# 4_54.net
KiCad netlist of a schematic drawn in EasyEDA
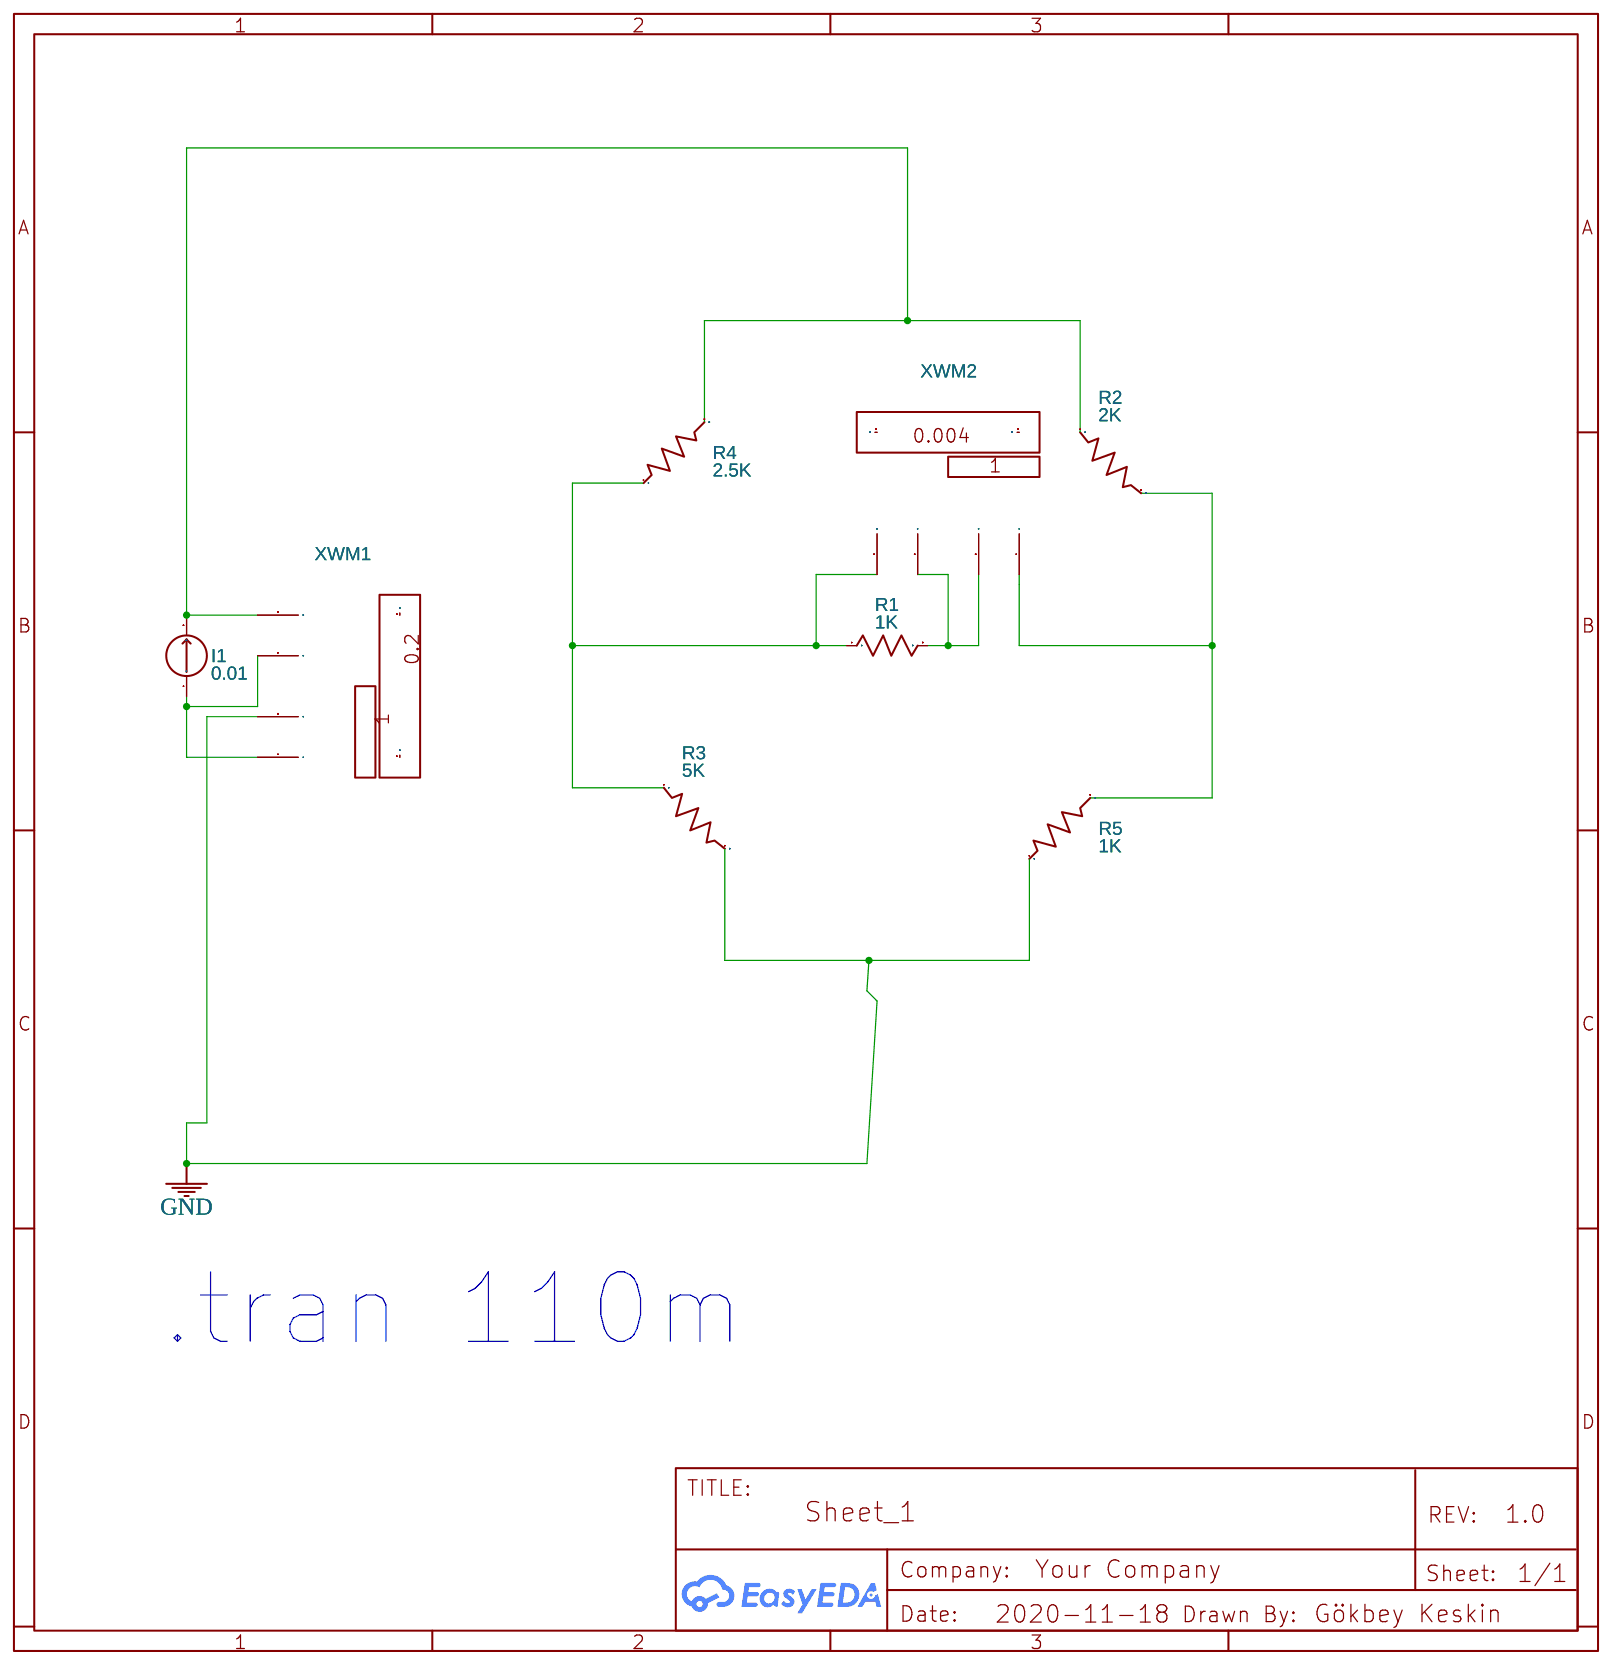
[diagram p0: schematic sheet]

(export (version "E")
  (design (tool "Eeschema 10.0.6"))
  (components
    (comp (ref "I1") (value "0.01") (libsource (lib "") (part "IDC")))
    (comp (ref "R1") (value "1K") (libsource (lib "") (part "Resistor_US")))
    (comp (ref "R2") (value "2K") (libsource (lib "") (part "Resistor_45Degree_US")))
    (comp (ref "R3") (value "5K") (libsource (lib "") (part "Resistor_45Degree_US")))
    (comp (ref "R4") (value "2.5K") (libsource (lib "") (part "Resistor_45Degree_US_1")))
    (comp (ref "R5") (value "1K") (libsource (lib "") (part "Resistor_45Degree_US_1")))
    (comp (ref "XWM1") (value "Wattmeter") (libsource (lib "") (part "WATTMETER_1")))
    (comp (ref "XWM2") (value "Wattmeter") (libsource (lib "") (part "WATTMETER")))
  )
  (nets
    (net (code "1") (name "GND") (class "Default")
      (node (ref "R3") (pin "2") (pinfunction "2_2") (pintype "unspecified"))
      (node (ref "R5") (pin "1") (pinfunction "1_1") (pintype "unspecified"))
      (node (ref "XWM1") (pin "3") (pinfunction "I+_3") (pintype "unspecified"))
    )
    (net (code "2") (name "Net-(XWM1-I-)") (class "Default")
      (node (ref "I1") (pin "1") (pinfunction "1_1") (pintype "unspecified"))
      (node (ref "XWM1") (pin "2") (pinfunction "V-_2") (pintype "unspecified"))
      (node (ref "XWM1") (pin "4") (pinfunction "I-_4") (pintype "unspecified"))
    )
    (net (code "3") (name "Net-(XWM1-V+)") (class "Default")
      (node (ref "I1") (pin "2") (pinfunction "2_2") (pintype "unspecified"))
      (node (ref "R2") (pin "1") (pinfunction "1_1") (pintype "unspecified"))
      (node (ref "R4") (pin "2") (pinfunction "2_2") (pintype "unspecified"))
      (node (ref "XWM1") (pin "1") (pinfunction "V+_1") (pintype "unspecified"))
    )
    (net (code "4") (name "Net-(XWM2-I+)") (class "Default")
      (node (ref "R1") (pin "2") (pinfunction "2_2") (pintype "unspecified"))
      (node (ref "XWM2") (pin "2") (pinfunction "V-_2") (pintype "unspecified"))
      (node (ref "XWM2") (pin "3") (pinfunction "I+_3") (pintype "unspecified"))
    )
    (net (code "5") (name "Net-(XWM2-I-)") (class "Default")
      (node (ref "R2") (pin "2") (pinfunction "2_2") (pintype "unspecified"))
      (node (ref "R5") (pin "2") (pinfunction "2_2") (pintype "unspecified"))
      (node (ref "XWM2") (pin "4") (pinfunction "I-_4") (pintype "unspecified"))
    )
    (net (code "6") (name "Net-(XWM2-V+)") (class "Default")
      (node (ref "R1") (pin "1") (pinfunction "1_1") (pintype "unspecified"))
      (node (ref "R3") (pin "1") (pinfunction "1_1") (pintype "unspecified"))
      (node (ref "R4") (pin "1") (pinfunction "1_1") (pintype "unspecified"))
      (node (ref "XWM2") (pin "1") (pinfunction "V+_1") (pintype "unspecified"))
    )
    (net (code "7") (name "unconnected-(XWM1-PadP)") (class "Default")
      (node (ref "XWM1") (pin "P") (pinfunction "P_P") (pintype "unspecified"))
    )
    (net (code "8") (name "unconnected-(XWM1-PadPF)") (class "Default")
      (node (ref "XWM1") (pin "PF") (pinfunction "PF_PF") (pintype "unspecified"))
    )
    (net (code "9") (name "unconnected-(XWM2-PadP)") (class "Default")
      (node (ref "XWM2") (pin "P") (pinfunction "P_P") (pintype "unspecified"))
    )
    (net (code "10") (name "unconnected-(XWM2-PadPF)") (class "Default")
      (node (ref "XWM2") (pin "PF") (pinfunction "PF_PF") (pintype "unspecified"))
    )
  )
)
